# stranger_things_badge.net
KiCad netlist of a schematic drawn in EAGLE
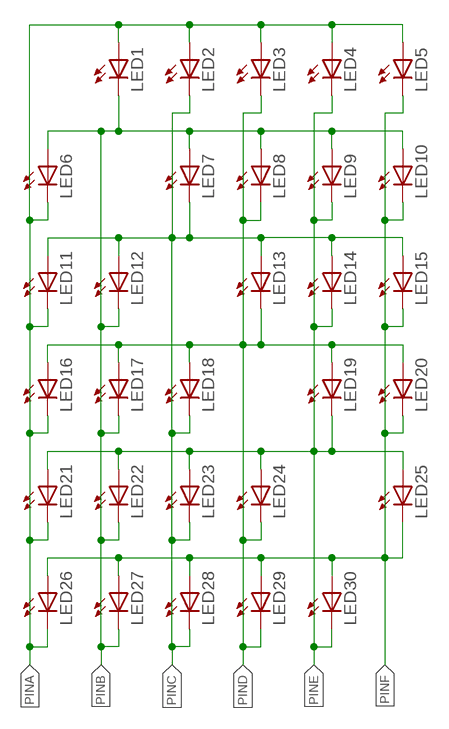
[diagram p0: schematic, sheet 1]

(export (version "E")
  (design (tool "Eeschema 10.0.6"))
  (components
    (comp (ref "LED1")
      (value "LEDCHIPLED_0805")
      (footprint "eagle-import:CHIPLED_0805")
      (libsource (lib "eagle-import") (part "LEDCHIPLED_0805"))
    )
    (comp (ref "LED2")
      (value "LEDSTRANGELED")
      (footprint "eagle-import:CHIPLED_0805_BS")
      (libsource (lib "eagle-import") (part "LEDSTRANGELED"))
    )
    (comp (ref "LED3")
      (value "LEDSTRANGELED")
      (footprint "eagle-import:CHIPLED_0805_BS")
      (libsource (lib "eagle-import") (part "LEDSTRANGELED"))
    )
    (comp (ref "LED4")
      (value "LEDSTRANGELED")
      (footprint "eagle-import:CHIPLED_0805_BS")
      (libsource (lib "eagle-import") (part "LEDSTRANGELED"))
    )
    (comp (ref "LED5")
      (value "LEDSTRANGELED")
      (footprint "eagle-import:CHIPLED_0805_BS")
      (libsource (lib "eagle-import") (part "LEDSTRANGELED"))
    )
    (comp (ref "LED6")
      (value "LEDSTRANGELED")
      (footprint "eagle-import:CHIPLED_0805_BS")
      (libsource (lib "eagle-import") (part "LEDSTRANGELED"))
    )
    (comp (ref "LED7")
      (value "LEDSTRANGELED")
      (footprint "eagle-import:CHIPLED_0805_BS")
      (libsource (lib "eagle-import") (part "LEDSTRANGELED"))
    )
    (comp (ref "LED8")
      (value "LEDSTRANGELED")
      (footprint "eagle-import:CHIPLED_0805_BS")
      (libsource (lib "eagle-import") (part "LEDSTRANGELED"))
    )
    (comp (ref "LED9")
      (value "LEDSTRANGELED")
      (footprint "eagle-import:CHIPLED_0805_BS")
      (libsource (lib "eagle-import") (part "LEDSTRANGELED"))
    )
    (comp (ref "LED10")
      (value "LEDSTRANGELED")
      (footprint "eagle-import:CHIPLED_0805_BS")
      (libsource (lib "eagle-import") (part "LEDSTRANGELED"))
    )
    (comp (ref "LED11")
      (value "LEDCHIPLED_0805")
      (footprint "eagle-import:CHIPLED_0805")
      (libsource (lib "eagle-import") (part "LEDCHIPLED_0805"))
    )
    (comp (ref "LED12")
      (value "LEDSTRANGELED")
      (footprint "eagle-import:CHIPLED_0805_BS")
      (libsource (lib "eagle-import") (part "LEDSTRANGELED"))
    )
    (comp (ref "LED13")
      (value "LEDSTRANGELED")
      (footprint "eagle-import:CHIPLED_0805_BS")
      (libsource (lib "eagle-import") (part "LEDSTRANGELED"))
    )
    (comp (ref "LED14")
      (value "LEDSTRANGELED")
      (footprint "eagle-import:CHIPLED_0805_BS")
      (libsource (lib "eagle-import") (part "LEDSTRANGELED"))
    )
    (comp (ref "LED15")
      (value "LEDSTRANGELED")
      (footprint "eagle-import:CHIPLED_0805_BS")
      (libsource (lib "eagle-import") (part "LEDSTRANGELED"))
    )
    (comp (ref "LED16")
      (value "LEDSTRANGELED")
      (footprint "eagle-import:CHIPLED_0805_BS")
      (libsource (lib "eagle-import") (part "LEDSTRANGELED"))
    )
    (comp (ref "LED17")
      (value "LEDSTRANGELED")
      (footprint "eagle-import:CHIPLED_0805_BS")
      (libsource (lib "eagle-import") (part "LEDSTRANGELED"))
    )
    (comp (ref "LED18")
      (value "LEDSTRANGELED")
      (footprint "eagle-import:CHIPLED_0805_BS")
      (libsource (lib "eagle-import") (part "LEDSTRANGELED"))
    )
    (comp (ref "LED19")
      (value "LEDSTRANGELED")
      (footprint "eagle-import:CHIPLED_0805_BS")
      (libsource (lib "eagle-import") (part "LEDSTRANGELED"))
    )
    (comp (ref "LED20")
      (value "LEDCHIPLED_0805")
      (footprint "eagle-import:CHIPLED_0805")
      (libsource (lib "eagle-import") (part "LEDCHIPLED_0805"))
    )
    (comp (ref "LED21")
      (value "LEDSTRANGELED")
      (footprint "eagle-import:CHIPLED_0805_BS")
      (libsource (lib "eagle-import") (part "LEDSTRANGELED"))
    )
    (comp (ref "LED22")
      (value "LEDSTRANGELED")
      (footprint "eagle-import:CHIPLED_0805_BS")
      (libsource (lib "eagle-import") (part "LEDSTRANGELED"))
    )
    (comp (ref "LED23")
      (value "LEDSTRANGELED")
      (footprint "eagle-import:CHIPLED_0805_BS")
      (libsource (lib "eagle-import") (part "LEDSTRANGELED"))
    )
    (comp (ref "LED24")
      (value "LEDCHIPLED_0805")
      (footprint "eagle-import:CHIPLED_0805")
      (libsource (lib "eagle-import") (part "LEDCHIPLED_0805"))
    )
    (comp (ref "LED25")
      (value "LEDSTRANGELED")
      (footprint "eagle-import:CHIPLED_0805_BS")
      (libsource (lib "eagle-import") (part "LEDSTRANGELED"))
    )
    (comp (ref "LED26")
      (value "LEDSTRANGELED")
      (footprint "eagle-import:CHIPLED_0805_BS")
      (libsource (lib "eagle-import") (part "LEDSTRANGELED"))
    )
    (comp (ref "LED27")
      (value "LEDSTRANGELED")
      (footprint "eagle-import:CHIPLED_0805_BS")
      (libsource (lib "eagle-import") (part "LEDSTRANGELED"))
    )
    (comp (ref "LED28")
      (value "LEDSTRANGELED")
      (footprint "eagle-import:CHIPLED_0805_BS")
      (libsource (lib "eagle-import") (part "LEDSTRANGELED"))
    )
    (comp (ref "LED29")
      (value "LEDSTRANGELED")
      (footprint "eagle-import:CHIPLED_0805_BS")
      (libsource (lib "eagle-import") (part "LEDSTRANGELED"))
    )
    (comp (ref "LED30")
      (value "LEDSTRANGELED")
      (footprint "eagle-import:CHIPLED_0805_BS")
      (libsource (lib "eagle-import") (part "LEDSTRANGELED"))
    )
  )
  (nets
    (net (code "1") (name "PINA") (class "Default")
      (node (ref "LED1") (pin "A") (pinfunction "A_A") (pintype "passive"))
      (node (ref "LED11") (pin "C") (pinfunction "C_C") (pintype "passive"))
      (node (ref "LED16") (pin "C") (pinfunction "C_C") (pintype "passive"))
      (node (ref "LED2") (pin "A") (pinfunction "A_A") (pintype "passive"))
      (node (ref "LED21") (pin "C") (pinfunction "C_C") (pintype "passive"))
      (node (ref "LED26") (pin "C") (pinfunction "C_C") (pintype "passive"))
      (node (ref "LED3") (pin "A") (pinfunction "A_A") (pintype "passive"))
      (node (ref "LED4") (pin "A") (pinfunction "A_A") (pintype "passive"))
      (node (ref "LED5") (pin "A") (pinfunction "A_A") (pintype "passive"))
      (node (ref "LED6") (pin "C") (pinfunction "C_C") (pintype "passive"))
    )
    (net (code "2") (name "PINB") (class "Default")
      (node (ref "LED1") (pin "C") (pinfunction "C_C") (pintype "passive"))
      (node (ref "LED10") (pin "A") (pinfunction "A_A") (pintype "passive"))
      (node (ref "LED12") (pin "C") (pinfunction "C_C") (pintype "passive"))
      (node (ref "LED17") (pin "C") (pinfunction "C_C") (pintype "passive"))
      (node (ref "LED22") (pin "C") (pinfunction "C_C") (pintype "passive"))
      (node (ref "LED27") (pin "C") (pinfunction "C_C") (pintype "passive"))
      (node (ref "LED6") (pin "A") (pinfunction "A_A") (pintype "passive"))
      (node (ref "LED7") (pin "A") (pinfunction "A_A") (pintype "passive"))
      (node (ref "LED8") (pin "A") (pinfunction "A_A") (pintype "passive"))
      (node (ref "LED9") (pin "A") (pinfunction "A_A") (pintype "passive"))
    )
    (net (code "3") (name "PINC") (class "Default")
      (node (ref "LED11") (pin "A") (pinfunction "A_A") (pintype "passive"))
      (node (ref "LED12") (pin "A") (pinfunction "A_A") (pintype "passive"))
      (node (ref "LED13") (pin "A") (pinfunction "A_A") (pintype "passive"))
      (node (ref "LED14") (pin "A") (pinfunction "A_A") (pintype "passive"))
      (node (ref "LED15") (pin "A") (pinfunction "A_A") (pintype "passive"))
      (node (ref "LED18") (pin "C") (pinfunction "C_C") (pintype "passive"))
      (node (ref "LED2") (pin "C") (pinfunction "C_C") (pintype "passive"))
      (node (ref "LED23") (pin "C") (pinfunction "C_C") (pintype "passive"))
      (node (ref "LED28") (pin "C") (pinfunction "C_C") (pintype "passive"))
      (node (ref "LED7") (pin "C") (pinfunction "C_C") (pintype "passive"))
    )
    (net (code "4") (name "PIND") (class "Default")
      (node (ref "LED13") (pin "C") (pinfunction "C_C") (pintype "passive"))
      (node (ref "LED16") (pin "A") (pinfunction "A_A") (pintype "passive"))
      (node (ref "LED17") (pin "A") (pinfunction "A_A") (pintype "passive"))
      (node (ref "LED18") (pin "A") (pinfunction "A_A") (pintype "passive"))
      (node (ref "LED19") (pin "A") (pinfunction "A_A") (pintype "passive"))
      (node (ref "LED20") (pin "A") (pinfunction "A_A") (pintype "passive"))
      (node (ref "LED24") (pin "C") (pinfunction "C_C") (pintype "passive"))
      (node (ref "LED29") (pin "C") (pinfunction "C_C") (pintype "passive"))
      (node (ref "LED3") (pin "C") (pinfunction "C_C") (pintype "passive"))
      (node (ref "LED8") (pin "C") (pinfunction "C_C") (pintype "passive"))
    )
    (net (code "5") (name "PINE") (class "Default")
      (node (ref "LED14") (pin "C") (pinfunction "C_C") (pintype "passive"))
      (node (ref "LED19") (pin "C") (pinfunction "C_C") (pintype "passive"))
      (node (ref "LED21") (pin "A") (pinfunction "A_A") (pintype "passive"))
      (node (ref "LED22") (pin "A") (pinfunction "A_A") (pintype "passive"))
      (node (ref "LED23") (pin "A") (pinfunction "A_A") (pintype "passive"))
      (node (ref "LED24") (pin "A") (pinfunction "A_A") (pintype "passive"))
      (node (ref "LED25") (pin "A") (pinfunction "A_A") (pintype "passive"))
      (node (ref "LED30") (pin "C") (pinfunction "C_C") (pintype "passive"))
      (node (ref "LED4") (pin "C") (pinfunction "C_C") (pintype "passive"))
      (node (ref "LED9") (pin "C") (pinfunction "C_C") (pintype "passive"))
    )
    (net (code "6") (name "PINF") (class "Default")
      (node (ref "LED10") (pin "C") (pinfunction "C_C") (pintype "passive"))
      (node (ref "LED15") (pin "C") (pinfunction "C_C") (pintype "passive"))
      (node (ref "LED20") (pin "C") (pinfunction "C_C") (pintype "passive"))
      (node (ref "LED25") (pin "C") (pinfunction "C_C") (pintype "passive"))
      (node (ref "LED26") (pin "A") (pinfunction "A_A") (pintype "passive"))
      (node (ref "LED27") (pin "A") (pinfunction "A_A") (pintype "passive"))
      (node (ref "LED28") (pin "A") (pinfunction "A_A") (pintype "passive"))
      (node (ref "LED29") (pin "A") (pinfunction "A_A") (pintype "passive"))
      (node (ref "LED30") (pin "A") (pinfunction "A_A") (pintype "passive"))
      (node (ref "LED5") (pin "C") (pinfunction "C_C") (pintype "passive"))
    )
  )
)
